# Prototype_0_1.net
KiCad netlist of a schematic drawn in EAGLE
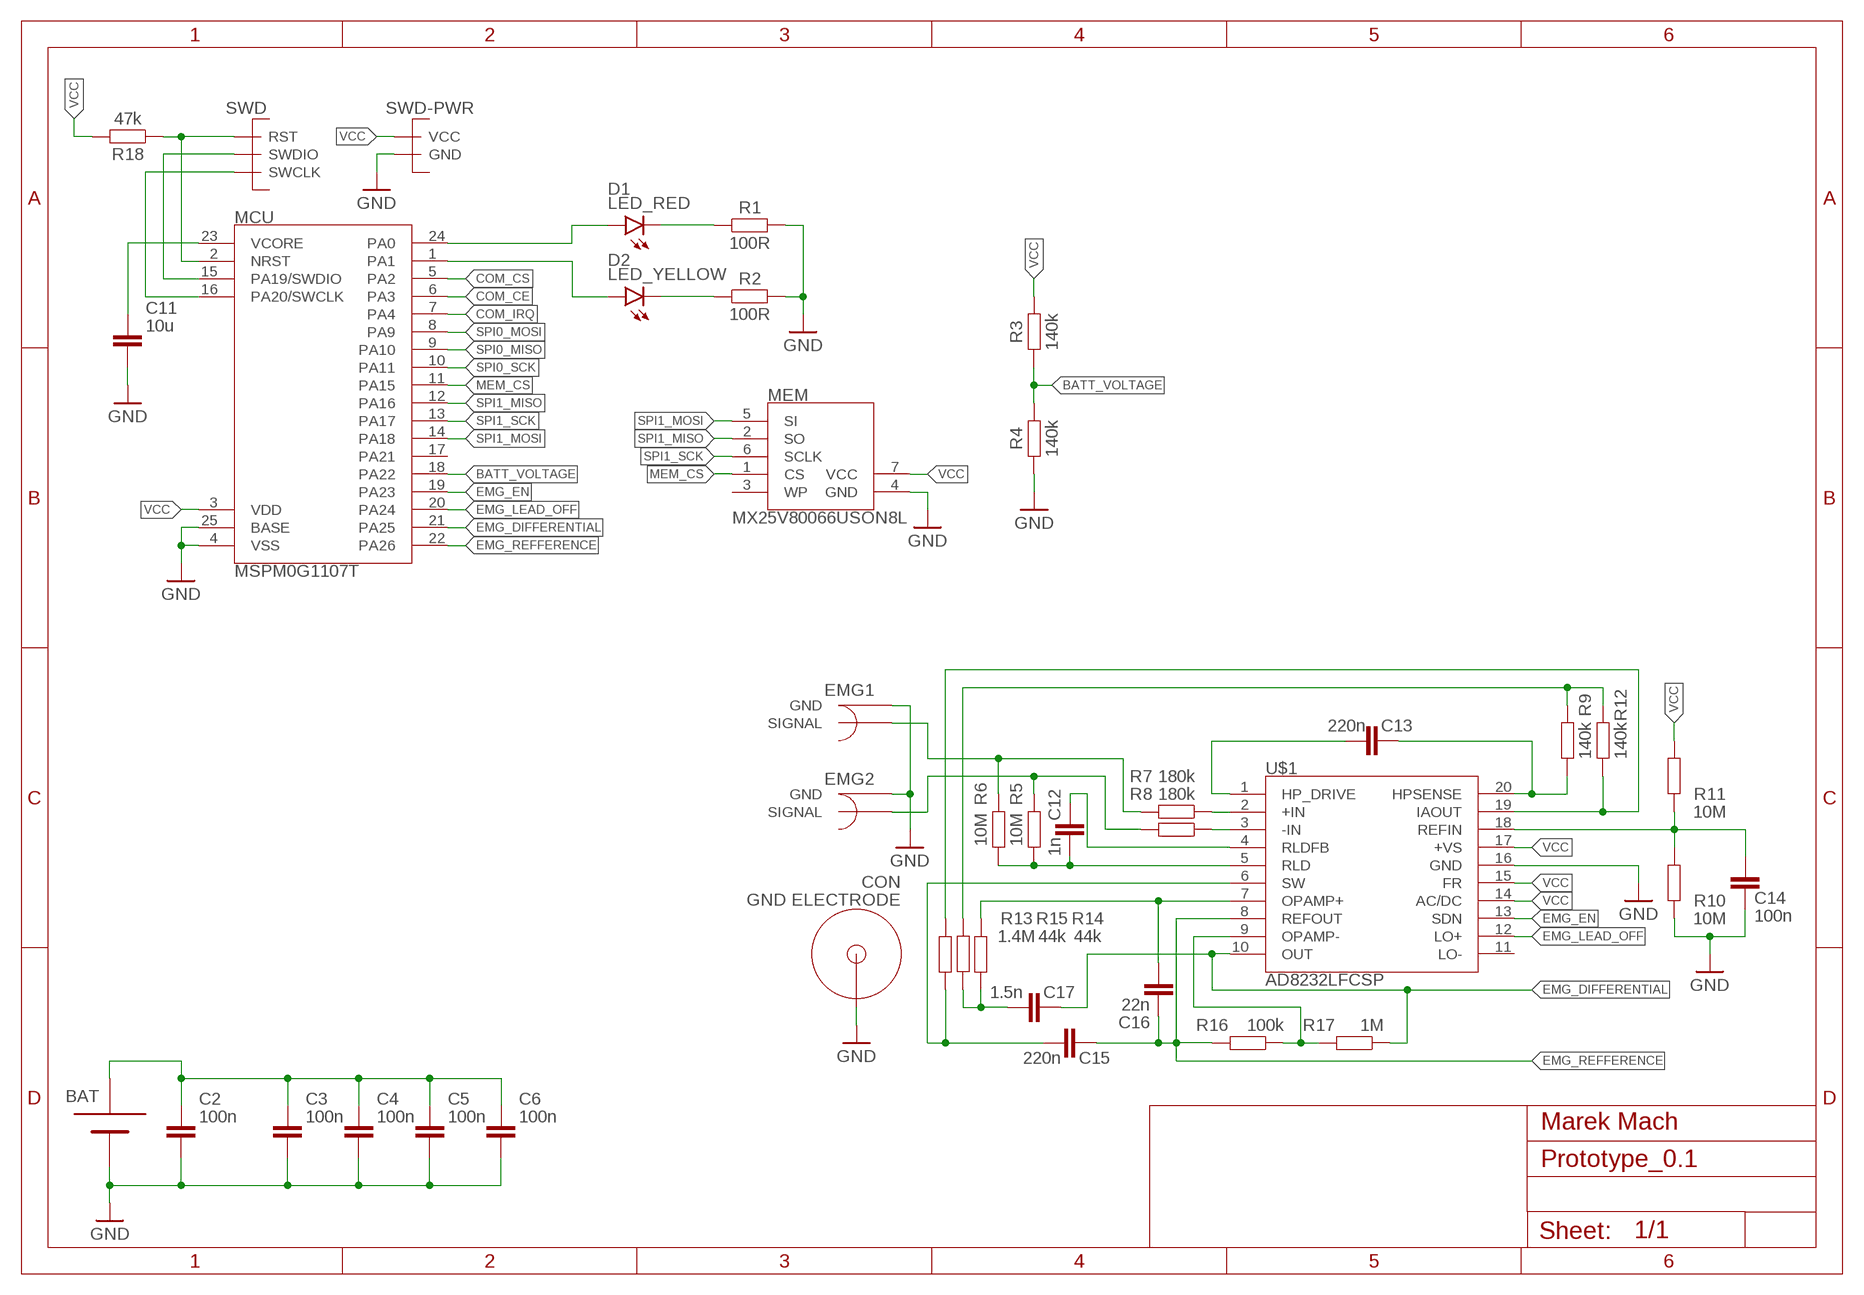
[diagram p0: schematic, sheet 1]

(export (version "E")
  (design (tool "Eeschema 10.0.6"))
  (components
    (comp (ref "BAT")
      (value "2025BAT-HLD-005-THM")
      (footprint "eagle-import:BAT-HLD-005-THM")
      (libsource (lib "eagle-import") (part "2025BAT-HLD-005-THM"))
    )
    (comp (ref "C2")
      (value "100n")
      (footprint "eagle-import:CAPC1608X85")
      (libsource (lib "eagle-import") (part "CCHIP-0603(1608-METRIC)_"))
    )
    (comp (ref "C3")
      (value "100n")
      (footprint "eagle-import:CAPC1608X85")
      (libsource (lib "eagle-import") (part "CCHIP-0603(1608-METRIC)_"))
    )
    (comp (ref "C4")
      (value "100n")
      (footprint "eagle-import:CAPC1608X85")
      (libsource (lib "eagle-import") (part "CCHIP-0603(1608-METRIC)_"))
    )
    (comp (ref "C5")
      (value "100n")
      (footprint "eagle-import:CAPC1608X85")
      (libsource (lib "eagle-import") (part "CCHIP-0603(1608-METRIC)_"))
    )
    (comp (ref "C6")
      (value "100n")
      (footprint "eagle-import:CAPC1608X85")
      (libsource (lib "eagle-import") (part "CCHIP-0603(1608-METRIC)_"))
    )
    (comp (ref "C11")
      (value "10u")
      (footprint "eagle-import:CAPC1608X85")
      (libsource (lib "eagle-import") (part "CCHIP-0603(1608-METRIC)_"))
    )
    (comp (ref "C12")
      (value "1n")
      (footprint "eagle-import:CAPC1608X85")
      (libsource (lib "eagle-import") (part "CCHIP-0603(1608-METRIC)_"))
    )
    (comp (ref "C13")
      (value "220n")
      (footprint "eagle-import:CAPC1608X85")
      (libsource (lib "eagle-import") (part "CCHIP-0603(1608-METRIC)_"))
    )
    (comp (ref "C14")
      (value "100n")
      (footprint "eagle-import:CAPC1608X85")
      (libsource (lib "eagle-import") (part "CCHIP-0603(1608-METRIC)_"))
    )
    (comp (ref "C15")
      (value "220n")
      (footprint "eagle-import:CAPC1608X85")
      (libsource (lib "eagle-import") (part "CCHIP-0603(1608-METRIC)_"))
    )
    (comp (ref "C16")
      (value "22n")
      (footprint "eagle-import:CAPC1608X85")
      (libsource (lib "eagle-import") (part "CCHIP-0603(1608-METRIC)_"))
    )
    (comp (ref "C17")
      (value "1.5n")
      (footprint "eagle-import:CAPC1608X85")
      (libsource (lib "eagle-import") (part "CCHIP-0603(1608-METRIC)_"))
    )
    (comp (ref "CON")
      (value "GND ELECTRODE")
      (footprint "eagle-import:ELECTRODE_CONNECTOR")
      (libsource (lib "eagle-import") (part "ECG_ELECTRODE_CONNECTOR"))
    )
    (comp (ref "D1")
      (value "LED_RED")
      (footprint "eagle-import:LEDC1005X25N_FLAT-R")
      (libsource (lib "eagle-import") (part "CHIP-FLAT-R_0402"))
    )
    (comp (ref "D2")
      (value "LED_YELLOW")
      (footprint "eagle-import:LEDC1005X25N_FLAT-Y")
      (libsource (lib "eagle-import") (part "CHIP-FLAT-Y_0402"))
    )
    (comp (ref "EMG1")
      (value "SHIELDED-CONNECTOR")
      (footprint "eagle-import:SHIELDED-SMD")
      (libsource (lib "eagle-import") (part "SHIELDED-CONNECTOR"))
    )
    (comp (ref "EMG2")
      (value "SHIELDED-CONNECTOR")
      (footprint "eagle-import:SHIELDED-SMD")
      (libsource (lib "eagle-import") (part "SHIELDED-CONNECTOR"))
    )
    (comp (ref "MCU")
      (value "MSPM0G1107T")
      (footprint "eagle-import:QFN50P400X400X100-25T240")
      (libsource (lib "eagle-import") (part "MSPM0G1107VQFN24-ROUNDPADS"))
    )
    (comp (ref "MEM")
      (value "MX25V80066USON8L")
      (footprint "eagle-import:SON50P300X200X50-8")
      (libsource (lib "eagle-import") (part "MX25V80066USON8L"))
    )
    (comp (ref "R1")
      (value "100R")
      (footprint "eagle-import:RESC1608X60")
      (libsource (lib "eagle-import") (part "RCHIP-0603(1608-METRIC)_"))
    )
    (comp (ref "R2")
      (value "100R")
      (footprint "eagle-import:RESC1608X60")
      (libsource (lib "eagle-import") (part "RCHIP-0603(1608-METRIC)_"))
    )
    (comp (ref "R3")
      (value "140k")
      (footprint "eagle-import:RESC1608X60")
      (libsource (lib "eagle-import") (part "RCHIP-0603(1608-METRIC)_"))
    )
    (comp (ref "R4")
      (value "140k")
      (footprint "eagle-import:RESC1608X60")
      (libsource (lib "eagle-import") (part "RCHIP-0603(1608-METRIC)_"))
    )
    (comp (ref "R5")
      (value "10M")
      (footprint "eagle-import:RESC1608X60")
      (libsource (lib "eagle-import") (part "RCHIP-0603(1608-METRIC)_"))
    )
    (comp (ref "R6")
      (value "10M")
      (footprint "eagle-import:RESC1608X60")
      (libsource (lib "eagle-import") (part "RCHIP-0603(1608-METRIC)_"))
    )
    (comp (ref "R7")
      (value "180k")
      (footprint "eagle-import:RESC1608X60")
      (libsource (lib "eagle-import") (part "RCHIP-0603(1608-METRIC)_"))
    )
    (comp (ref "R8")
      (value "180k")
      (footprint "eagle-import:RESC1608X60")
      (libsource (lib "eagle-import") (part "RCHIP-0603(1608-METRIC)_"))
    )
    (comp (ref "R9")
      (value "140k")
      (footprint "eagle-import:RESC1608X60")
      (libsource (lib "eagle-import") (part "RCHIP-0603(1608-METRIC)_"))
    )
    (comp (ref "R10")
      (value "10M")
      (footprint "eagle-import:RESC1608X60")
      (libsource (lib "eagle-import") (part "RCHIP-0603(1608-METRIC)_"))
    )
    (comp (ref "R11")
      (value "10M")
      (footprint "eagle-import:RESC1608X60")
      (libsource (lib "eagle-import") (part "RCHIP-0603(1608-METRIC)_"))
    )
    (comp (ref "R12")
      (value "140k")
      (footprint "eagle-import:RESC1608X60")
      (libsource (lib "eagle-import") (part "RCHIP-0603(1608-METRIC)_"))
    )
    (comp (ref "R13")
      (value "1.4M")
      (footprint "eagle-import:RESC1608X60")
      (libsource (lib "eagle-import") (part "RCHIP-0603(1608-METRIC)_"))
    )
    (comp (ref "R14")
      (value "44k")
      (footprint "eagle-import:RESC1608X60")
      (libsource (lib "eagle-import") (part "RCHIP-0603(1608-METRIC)_"))
    )
    (comp (ref "R15")
      (value "44k")
      (footprint "eagle-import:RESC1608X60")
      (libsource (lib "eagle-import") (part "RCHIP-0603(1608-METRIC)_"))
    )
    (comp (ref "R16")
      (value "100k")
      (footprint "eagle-import:RESC1608X60")
      (libsource (lib "eagle-import") (part "RCHIP-0603(1608-METRIC)_"))
    )
    (comp (ref "R17")
      (value "1M")
      (footprint "eagle-import:RESC1608X60")
      (libsource (lib "eagle-import") (part "RCHIP-0603(1608-METRIC)_"))
    )
    (comp (ref "R18")
      (value "47k")
      (footprint "eagle-import:RESC1608X60")
      (libsource (lib "eagle-import") (part "RCHIP-0603(1608-METRIC)_"))
    )
    (comp (ref "SWD")
      (value "SWD")
      (footprint "eagle-import:3X")
      (libsource (lib "eagle-import") (part "SWD"))
    )
    (comp (ref "SWD-PWR")
      (value "PWR")
      (footprint "eagle-import:2X")
      (libsource (lib "eagle-import") (part "PWR"))
    )
    (comp (ref "U$1")
      (value "AD8232LFCSP")
      (footprint "eagle-import:QFN50P400X400X80-21T275")
      (libsource (lib "eagle-import") (part "AD8232LFCSP"))
    )
  )
  (nets
    (net (code "1") (name "BATT_VOLTAGE") (class "Default")
      (node (ref "MCU") (pin "18") (pinfunction "PA22_18") (pintype "bidirectional"))
      (node (ref "R3") (pin "1") (pinfunction "1_1") (pintype "passive"))
      (node (ref "R4") (pin "2") (pinfunction "2_2") (pintype "passive"))
    )
    (net (code "2") (name "COM_CE") (class "Default")
      (node (ref "MCU") (pin "6") (pinfunction "PA3_6") (pintype "bidirectional"))
    )
    (net (code "3") (name "COM_CS") (class "Default")
      (node (ref "MCU") (pin "5") (pinfunction "PA2_5") (pintype "bidirectional"))
    )
    (net (code "4") (name "COM_IRQ") (class "Default")
      (node (ref "MCU") (pin "7") (pinfunction "PA4_7") (pintype "bidirectional"))
    )
    (net (code "5") (name "EMG_DIFFERENTIAL") (class "Default")
      (node (ref "C17") (pin "2") (pinfunction "2_2") (pintype "passive"))
      (node (ref "MCU") (pin "21") (pinfunction "PA25_21") (pintype "bidirectional"))
      (node (ref "R17") (pin "1") (pinfunction "1_1") (pintype "passive"))
      (node (ref "U$1") (pin "10") (pinfunction "OUT_10") (pintype "bidirectional"))
    )
    (net (code "6") (name "EMG_EN") (class "Default")
      (node (ref "MCU") (pin "19") (pinfunction "PA23_19") (pintype "bidirectional"))
      (node (ref "U$1") (pin "13") (pinfunction "SDN_13") (pintype "bidirectional"))
    )
    (net (code "7") (name "EMG_LEAD_OFF") (class "Default")
      (node (ref "MCU") (pin "20") (pinfunction "PA24_20") (pintype "bidirectional"))
      (node (ref "U$1") (pin "12") (pinfunction "LO+_12") (pintype "bidirectional"))
    )
    (net (code "8") (name "EMG_REFFERENCE") (class "Default")
      (node (ref "C15") (pin "2") (pinfunction "2_2") (pintype "passive"))
      (node (ref "C16") (pin "1") (pinfunction "1_1") (pintype "passive"))
      (node (ref "MCU") (pin "22") (pinfunction "PA26_22") (pintype "bidirectional"))
      (node (ref "R16") (pin "2") (pinfunction "2_2") (pintype "passive"))
      (node (ref "U$1") (pin "8") (pinfunction "REFOUT_8") (pintype "bidirectional"))
    )
    (net (code "9") (name "GND") (class "Default")
      (node (ref "BAT") (pin "P$1") (pinfunction "-_P$1") (pintype "bidirectional"))
      (node (ref "C11") (pin "2") (pinfunction "2_2") (pintype "passive"))
      (node (ref "C14") (pin "1") (pinfunction "1_1") (pintype "passive"))
      (node (ref "C2") (pin "2") (pinfunction "2_2") (pintype "passive"))
      (node (ref "C3") (pin "2") (pinfunction "2_2") (pintype "passive"))
      (node (ref "C4") (pin "2") (pinfunction "2_2") (pintype "passive"))
      (node (ref "C5") (pin "2") (pinfunction "2_2") (pintype "passive"))
      (node (ref "C6") (pin "2") (pinfunction "2_2") (pintype "passive"))
      (node (ref "CON") (pin "P$1") (pinfunction "P$1_P$1") (pintype "bidirectional"))
      (node (ref "CON") (pin "P$2") (pinfunction "P$1_P$2") (pintype "bidirectional"))
      (node (ref "CON") (pin "P$3") (pinfunction "P$1_P$3") (pintype "bidirectional"))
      (node (ref "CON") (pin "P$4") (pinfunction "P$1_P$4") (pintype "bidirectional"))
      (node (ref "EMG1") (pin "GND1") (pinfunction "GND_GND1") (pintype "bidirectional"))
      (node (ref "EMG1") (pin "GND2") (pinfunction "GND_GND2") (pintype "bidirectional"))
      (node (ref "EMG2") (pin "GND1") (pinfunction "GND_GND1") (pintype "bidirectional"))
      (node (ref "EMG2") (pin "GND2") (pinfunction "GND_GND2") (pintype "bidirectional"))
      (node (ref "MCU") (pin "25") (pinfunction "BASE_25") (pintype "bidirectional"))
      (node (ref "MCU") (pin "4") (pinfunction "VSS_4") (pintype "bidirectional"))
      (node (ref "MEM") (pin "4") (pinfunction "GND_4") (pintype "power_in"))
      (node (ref "R1") (pin "2") (pinfunction "2_2") (pintype "passive"))
      (node (ref "R10") (pin "1") (pinfunction "1_1") (pintype "passive"))
      (node (ref "R2") (pin "2") (pinfunction "2_2") (pintype "passive"))
      (node (ref "R4") (pin "1") (pinfunction "1_1") (pintype "passive"))
      (node (ref "SWD-PWR") (pin "1") (pinfunction "GND_1") (pintype "bidirectional"))
      (node (ref "U$1") (pin "16") (pinfunction "GND_16") (pintype "bidirectional"))
    )
    (net (code "10") (name "MEM_CS") (class "Default")
      (node (ref "MCU") (pin "11") (pinfunction "PA15_11") (pintype "bidirectional"))
      (node (ref "MEM") (pin "1") (pinfunction "CS_1") (pintype "bidirectional"))
    )
    (net (code "11") (name "Net-(C17-Pad1)") (class "Default")
      (node (ref "C17") (pin "1") (pinfunction "1_1") (pintype "passive"))
      (node (ref "R14") (pin "2") (pinfunction "2_2") (pintype "passive"))
      (node (ref "R15") (pin "1") (pinfunction "1_1") (pintype "passive"))
    )
    (net (code "12") (name "Net-(D1-PadC)") (class "Default")
      (node (ref "D1") (pin "C") (pinfunction "C_C") (pintype "passive"))
      (node (ref "R1") (pin "1") (pinfunction "1_1") (pintype "passive"))
    )
    (net (code "13") (name "Net-(D2-PadC)") (class "Default")
      (node (ref "D2") (pin "C") (pinfunction "C_C") (pintype "passive"))
      (node (ref "R2") (pin "1") (pinfunction "1_1") (pintype "passive"))
    )
    (net (code "14") (name "Net-(EMG1-SIGNAL)") (class "Default")
      (node (ref "EMG1") (pin "SIG") (pinfunction "SIGNAL_SIG") (pintype "bidirectional"))
      (node (ref "R6") (pin "2") (pinfunction "2_2") (pintype "passive"))
      (node (ref "R7") (pin "2") (pinfunction "2_2") (pintype "passive"))
    )
    (net (code "15") (name "Net-(EMG2-SIGNAL)") (class "Default")
      (node (ref "EMG2") (pin "SIG") (pinfunction "SIGNAL_SIG") (pintype "bidirectional"))
      (node (ref "R5") (pin "2") (pinfunction "2_2") (pintype "passive"))
      (node (ref "R8") (pin "2") (pinfunction "2_2") (pintype "passive"))
    )
    (net (code "16") (name "Net-(MCU-NRST)") (class "Default")
      (node (ref "MCU") (pin "2") (pinfunction "NRST_2") (pintype "bidirectional"))
      (node (ref "R18") (pin "1") (pinfunction "1_1") (pintype "passive"))
      (node (ref "SWD") (pin "1") (pinfunction "RST_1") (pintype "bidirectional"))
    )
    (net (code "17") (name "Net-(MCU-PA0)") (class "Default")
      (node (ref "D1") (pin "A") (pinfunction "A_A") (pintype "passive"))
      (node (ref "MCU") (pin "24") (pinfunction "PA0_24") (pintype "bidirectional"))
    )
    (net (code "18") (name "Net-(MCU-PA1)") (class "Default")
      (node (ref "D2") (pin "A") (pinfunction "A_A") (pintype "passive"))
      (node (ref "MCU") (pin "1") (pinfunction "PA1_1") (pintype "bidirectional"))
    )
    (net (code "19") (name "Net-(MCU-PA19{slash}SWDIO)") (class "Default")
      (node (ref "MCU") (pin "15") (pinfunction "PA19/SWDIO_15") (pintype "bidirectional"))
      (node (ref "SWD") (pin "2") (pinfunction "SWDIO_2") (pintype "bidirectional"))
    )
    (net (code "20") (name "Net-(MCU-PA20{slash}SWCLK)") (class "Default")
      (node (ref "MCU") (pin "16") (pinfunction "PA20/SWCLK_16") (pintype "bidirectional"))
      (node (ref "SWD") (pin "3") (pinfunction "SWCLK_3") (pintype "bidirectional"))
    )
    (net (code "21") (name "Net-(MCU-VCORE)") (class "Default")
      (node (ref "C11") (pin "1") (pinfunction "1_1") (pintype "passive"))
      (node (ref "MCU") (pin "23") (pinfunction "VCORE_23") (pintype "bidirectional"))
    )
    (net (code "22") (name "Net-(R12-Pad2)") (class "Default")
      (node (ref "R12") (pin "2") (pinfunction "2_2") (pintype "passive"))
      (node (ref "R15") (pin "2") (pinfunction "2_2") (pintype "passive"))
      (node (ref "R9") (pin "2") (pinfunction "2_2") (pintype "passive"))
    )
    (net (code "23") (name "Net-(U$1-+IN)") (class "Default")
      (node (ref "R7") (pin "1") (pinfunction "1_1") (pintype "passive"))
      (node (ref "U$1") (pin "2") (pinfunction "+IN_2") (pintype "bidirectional"))
    )
    (net (code "24") (name "Net-(U$1--IN)") (class "Default")
      (node (ref "R8") (pin "1") (pinfunction "1_1") (pintype "passive"))
      (node (ref "U$1") (pin "3") (pinfunction "-IN_3") (pintype "bidirectional"))
    )
    (net (code "25") (name "Net-(U$1-HPSENSE)") (class "Default")
      (node (ref "C13") (pin "2") (pinfunction "2_2") (pintype "passive"))
      (node (ref "R9") (pin "1") (pinfunction "1_1") (pintype "passive"))
      (node (ref "U$1") (pin "20") (pinfunction "HPSENSE_20") (pintype "bidirectional"))
    )
    (net (code "26") (name "Net-(U$1-HP_DRIVE)") (class "Default")
      (node (ref "C13") (pin "1") (pinfunction "1_1") (pintype "passive"))
      (node (ref "U$1") (pin "1") (pinfunction "HP_DRIVE_1") (pintype "bidirectional"))
    )
    (net (code "27") (name "Net-(U$1-IAOUT)") (class "Default")
      (node (ref "R12") (pin "1") (pinfunction "1_1") (pintype "passive"))
      (node (ref "R13") (pin "1") (pinfunction "1_1") (pintype "passive"))
      (node (ref "U$1") (pin "19") (pinfunction "IAOUT_19") (pintype "bidirectional"))
    )
    (net (code "28") (name "Net-(U$1-OPAMP+)") (class "Default")
      (node (ref "C16") (pin "2") (pinfunction "2_2") (pintype "passive"))
      (node (ref "R14") (pin "1") (pinfunction "1_1") (pintype "passive"))
      (node (ref "U$1") (pin "7") (pinfunction "OPAMP+_7") (pintype "bidirectional"))
    )
    (net (code "29") (name "Net-(U$1-OPAMP-)") (class "Default")
      (node (ref "R16") (pin "1") (pinfunction "1_1") (pintype "passive"))
      (node (ref "R17") (pin "2") (pinfunction "2_2") (pintype "passive"))
      (node (ref "U$1") (pin "9") (pinfunction "OPAMP-_9") (pintype "bidirectional"))
    )
    (net (code "30") (name "Net-(U$1-REFIN)") (class "Default")
      (node (ref "C14") (pin "2") (pinfunction "2_2") (pintype "passive"))
      (node (ref "R10") (pin "2") (pinfunction "2_2") (pintype "passive"))
      (node (ref "R11") (pin "1") (pinfunction "1_1") (pintype "passive"))
      (node (ref "U$1") (pin "18") (pinfunction "REFIN_18") (pintype "bidirectional"))
    )
    (net (code "31") (name "Net-(U$1-RLD)") (class "Default")
      (node (ref "C12") (pin "1") (pinfunction "1_1") (pintype "passive"))
      (node (ref "R5") (pin "1") (pinfunction "1_1") (pintype "passive"))
      (node (ref "R6") (pin "1") (pinfunction "1_1") (pintype "passive"))
      (node (ref "U$1") (pin "5") (pinfunction "RLD_5") (pintype "bidirectional"))
    )
    (net (code "32") (name "Net-(U$1-RLDFB)") (class "Default")
      (node (ref "C12") (pin "2") (pinfunction "2_2") (pintype "passive"))
      (node (ref "U$1") (pin "4") (pinfunction "RLDFB_4") (pintype "bidirectional"))
    )
    (net (code "33") (name "Net-(U$1-SW)") (class "Default")
      (node (ref "C15") (pin "1") (pinfunction "1_1") (pintype "passive"))
      (node (ref "R13") (pin "2") (pinfunction "2_2") (pintype "passive"))
      (node (ref "U$1") (pin "6") (pinfunction "SW_6") (pintype "bidirectional"))
    )
    (net (code "34") (name "SPI0_MISO") (class "Default")
      (node (ref "MCU") (pin "9") (pinfunction "PA10_9") (pintype "bidirectional"))
    )
    (net (code "35") (name "SPI0_MOSI") (class "Default")
      (node (ref "MCU") (pin "8") (pinfunction "PA9_8") (pintype "bidirectional"))
    )
    (net (code "36") (name "SPI0_SCK") (class "Default")
      (node (ref "MCU") (pin "10") (pinfunction "PA11_10") (pintype "bidirectional"))
    )
    (net (code "37") (name "SPI1_MISO") (class "Default")
      (node (ref "MCU") (pin "12") (pinfunction "PA16_12") (pintype "bidirectional"))
      (node (ref "MEM") (pin "2") (pinfunction "SO_2") (pintype "bidirectional"))
    )
    (net (code "38") (name "SPI1_MOSI") (class "Default")
      (node (ref "MCU") (pin "14") (pinfunction "PA18_14") (pintype "bidirectional"))
      (node (ref "MEM") (pin "5") (pinfunction "SI_5") (pintype "bidirectional"))
    )
    (net (code "39") (name "SPI1_SCK") (class "Default")
      (node (ref "MCU") (pin "13") (pinfunction "PA17_13") (pintype "bidirectional"))
      (node (ref "MEM") (pin "6") (pinfunction "SCLK_6") (pintype "bidirectional"))
    )
    (net (code "40") (name "VCC") (class "Default")
      (node (ref "BAT") (pin "P$2") (pinfunction "+_P$2") (pintype "bidirectional"))
      (node (ref "BAT") (pin "P$3") (pinfunction "+_P$3") (pintype "bidirectional"))
      (node (ref "C2") (pin "1") (pinfunction "1_1") (pintype "passive"))
      (node (ref "C3") (pin "1") (pinfunction "1_1") (pintype "passive"))
      (node (ref "C4") (pin "1") (pinfunction "1_1") (pintype "passive"))
      (node (ref "C5") (pin "1") (pinfunction "1_1") (pintype "passive"))
      (node (ref "C6") (pin "1") (pinfunction "1_1") (pintype "passive"))
      (node (ref "MCU") (pin "3") (pinfunction "VDD_3") (pintype "bidirectional"))
      (node (ref "MEM") (pin "7") (pinfunction "VCC_7") (pintype "power_in"))
      (node (ref "R11") (pin "2") (pinfunction "2_2") (pintype "passive"))
      (node (ref "R18") (pin "2") (pinfunction "2_2") (pintype "passive"))
      (node (ref "R3") (pin "2") (pinfunction "2_2") (pintype "passive"))
      (node (ref "SWD-PWR") (pin "2") (pinfunction "VCC_2") (pintype "bidirectional"))
      (node (ref "U$1") (pin "14") (pinfunction "AC/DC_14") (pintype "bidirectional"))
      (node (ref "U$1") (pin "15") (pinfunction "FR_15") (pintype "bidirectional"))
      (node (ref "U$1") (pin "17") (pinfunction "+VS_17") (pintype "bidirectional"))
    )
    (net (code "41") (name "unconnected-(MCU-PA21-Pad17)") (class "Default")
      (node (ref "MCU") (pin "17") (pinfunction "PA21_17") (pintype "bidirectional"))
    )
    (net (code "42") (name "unconnected-(MEM-WP-Pad3)") (class "Default")
      (node (ref "MEM") (pin "3") (pinfunction "WP_3") (pintype "bidirectional"))
    )
    (net (code "43") (name "unconnected-(U$1-LO--Pad11)") (class "Default")
      (node (ref "U$1") (pin "11") (pinfunction "LO-_11") (pintype "bidirectional"))
    )
  )
)
